# PIC_backpack.net
KiCad netlist of a schematic drawn in EAGLE
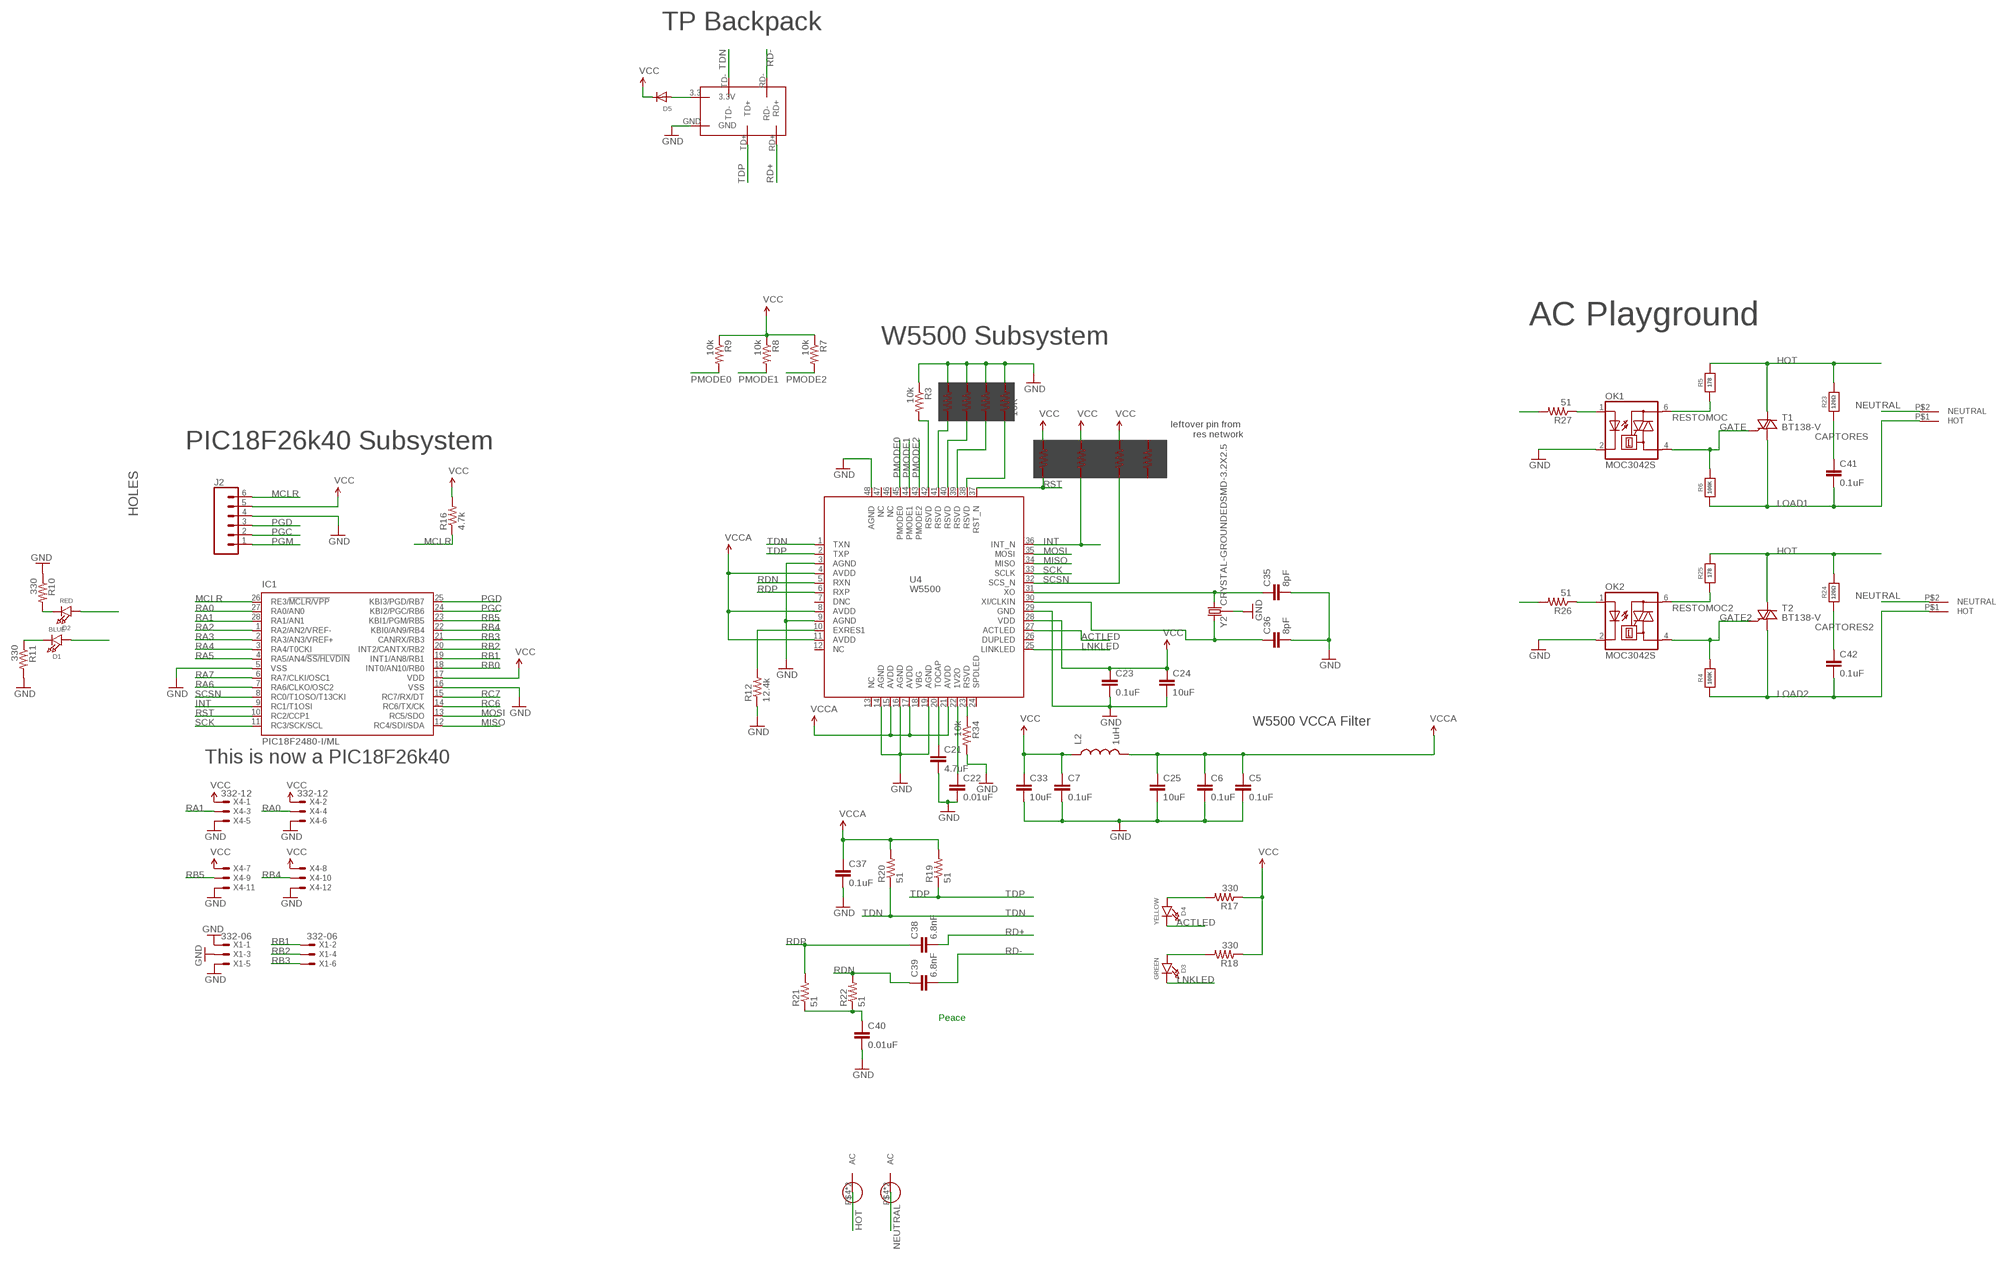
[diagram p0: schematic, sheet 1]

(export (version "E")
  (design (tool "Eeschema 10.0.6"))
  (components
    (comp (ref "C5")
      (value "0.1uF")
      (footprint "eagle-import:0603-CAP")
      (libsource (lib "eagle-import") (part "SparkFun-Passives_CAP0603-CAP"))
    )
    (comp (ref "C6")
      (value "0.1uF")
      (footprint "eagle-import:0603-CAP")
      (libsource (lib "eagle-import") (part "SparkFun-Passives_CAP0603-CAP"))
    )
    (comp (ref "C7")
      (value "0.1uF")
      (footprint "eagle-import:0603-CAP")
      (libsource (lib "eagle-import") (part "SparkFun-Passives_CAP0603-CAP"))
    )
    (comp (ref "C21")
      (value "4.7uF")
      (footprint "eagle-import:0603-CAP")
      (libsource (lib "eagle-import") (part "SparkFun-Passives_CAP0603-CAP"))
    )
    (comp (ref "C22")
      (value "0.01uF")
      (footprint "eagle-import:0603-CAP")
      (libsource (lib "eagle-import") (part "SparkFun-Passives_CAP0603-CAP"))
    )
    (comp (ref "C23")
      (value "0.1uF")
      (footprint "eagle-import:0603-CAP")
      (libsource (lib "eagle-import") (part "SparkFun-Passives_CAP0603-CAP"))
    )
    (comp (ref "C24")
      (value "10uF")
      (footprint "eagle-import:0603-CAP")
      (libsource (lib "eagle-import") (part "SparkFun-Passives_CAP0603-CAP"))
    )
    (comp (ref "C25")
      (value "10uF")
      (footprint "eagle-import:0603-CAP")
      (libsource (lib "eagle-import") (part "SparkFun-Passives_CAP0603-CAP"))
    )
    (comp (ref "C33")
      (value "10uF")
      (footprint "eagle-import:0603-CAP")
      (libsource (lib "eagle-import") (part "SparkFun-Passives_CAP0603-CAP"))
    )
    (comp (ref "C35")
      (value "8pF")
      (footprint "eagle-import:0603-CAP")
      (libsource (lib "eagle-import") (part "SparkFun-Passives_CAP0603-CAP"))
    )
    (comp (ref "C36")
      (value "8pF")
      (footprint "eagle-import:0603-CAP")
      (libsource (lib "eagle-import") (part "SparkFun-Passives_CAP0603-CAP"))
    )
    (comp (ref "C37")
      (value "0.1uF")
      (footprint "eagle-import:0603-CAP")
      (libsource (lib "eagle-import") (part "SparkFun-Passives_CAP0603-CAP"))
    )
    (comp (ref "C38")
      (value "6.8nF")
      (footprint "eagle-import:0603-CAP")
      (libsource (lib "eagle-import") (part "SparkFun-Passives_CAP0603-CAP"))
    )
    (comp (ref "C39")
      (value "6.8nF")
      (footprint "eagle-import:0603-CAP")
      (libsource (lib "eagle-import") (part "SparkFun-Passives_CAP0603-CAP"))
    )
    (comp (ref "C40")
      (value "0.01uF")
      (footprint "eagle-import:0603-CAP")
      (libsource (lib "eagle-import") (part "SparkFun-Passives_CAP0603-CAP"))
    )
    (comp (ref "C41")
      (value "0.1uF")
      (footprint "eagle-import:1210")
      (libsource (lib "eagle-import") (part "CAP1210"))
    )
    (comp (ref "C42")
      (value "0.1uF")
      (footprint "eagle-import:1210")
      (libsource (lib "eagle-import") (part "CAP1210"))
    )
    (comp (ref "D1")
      (value "BLUE")
      (footprint "eagle-import:CHIPLED_0603_NOOUTLINE")
      (libsource (lib "eagle-import") (part "LED0603_NOOUTLINE"))
    )
    (comp (ref "D2")
      (value "RED")
      (footprint "eagle-import:CHIPLED_0603_NOOUTLINE")
      (libsource (lib "eagle-import") (part "LED0603_NOOUTLINE"))
    )
    (comp (ref "D3")
      (value "GREEN")
      (footprint "eagle-import:CHIPLED_0603_NOOUTLINE")
      (libsource (lib "eagle-import") (part "LED0603_NOOUTLINE"))
    )
    (comp (ref "D4")
      (value "YELLOW")
      (footprint "eagle-import:CHIPLED_0603_NOOUTLINE")
      (libsource (lib "eagle-import") (part "LED0603_NOOUTLINE"))
    )
    (comp (ref "D5")
      (value "DIODESOD-123")
      (footprint "eagle-import:SOD-123")
      (libsource (lib "eagle-import") (part "DIODESOD-123"))
    )
    (comp (ref "IC1")
      (value "PIC18F2480-I/ML")
      (footprint "eagle-import:QFN28-ML_6X6MM")
      (fields (field (name "MF") "MICROCHIP"))
      (libsource (lib "eagle-import") (part "PIC18F280-I/ML4"))
    )
    (comp (ref "J2")
      (value "CONN_06NO_SILK_FEMALE_PTH")
      (footprint "eagle-import:1X06_NO_SILK")
      (libsource (lib "eagle-import") (part "CONN_06NO_SILK_FEMALE_PTH"))
    )
    (comp (ref "L2")
      (value "1uH")
      (footprint "eagle-import:0603")
      (libsource (lib "eagle-import") (part "INDUCTOR0603"))
    )
    (comp (ref "OK1")
      (value "MOC3042S")
      (footprint "eagle-import:DIL6-SMD")
      (fields (field (name "MF") "FAIRCHILD SEMICONDUCTOR") (field (name "MPN") "MOC3042SM"))
      (libsource (lib "eagle-import") (part "MOC30S42"))
    )
    (comp (ref "OK2")
      (value "MOC3042S")
      (footprint "eagle-import:DIL6-SMD")
      (fields (field (name "MF") "FAIRCHILD SEMICONDUCTOR") (field (name "MPN") "MOC3042SM"))
      (libsource (lib "eagle-import") (part "MOC30S42"))
    )
    (comp (ref "R1")
      (value "10K")
      (footprint "eagle-import:RESPACK_4X0603")
      (libsource (lib "eagle-import") (part "RESISTOR_4PACK_US"))
    )
    (comp (ref "R2")
      (value "10K")
      (footprint "eagle-import:RESPACK_4X0603")
      (libsource (lib "eagle-import") (part "RESISTOR_4PACK_US"))
    )
    (comp (ref "R3")
      (value "10k")
      (footprint "eagle-import:0603-RES")
      (libsource (lib "eagle-import") (part "RESISTOR0603-RES"))
    )
    (comp (ref "R4")
      (value "100K")
      (footprint "eagle-import:0805_10MGAP")
      (libsource (lib "eagle-import") (part "RESISTOR0805_10MGAP"))
    )
    (comp (ref "R5")
      (value "178")
      (footprint "eagle-import:0805_10MGAP")
      (libsource (lib "eagle-import") (part "RESISTOR0805_10MGAP"))
    )
    (comp (ref "R6")
      (value "100K")
      (footprint "eagle-import:0805_10MGAP")
      (libsource (lib "eagle-import") (part "RESISTOR0805_10MGAP"))
    )
    (comp (ref "R7")
      (value "10k")
      (footprint "eagle-import:0603-RES")
      (libsource (lib "eagle-import") (part "RESISTOR0603-RES"))
    )
    (comp (ref "R8")
      (value "10k")
      (footprint "eagle-import:0603-RES")
      (libsource (lib "eagle-import") (part "RESISTOR0603-RES"))
    )
    (comp (ref "R9")
      (value "10k")
      (footprint "eagle-import:0603-RES")
      (libsource (lib "eagle-import") (part "RESISTOR0603-RES"))
    )
    (comp (ref "R10")
      (value "330")
      (footprint "eagle-import:0603-RES")
      (libsource (lib "eagle-import") (part "RESISTOR0603-RES"))
    )
    (comp (ref "R11")
      (value "330")
      (footprint "eagle-import:0603-RES")
      (libsource (lib "eagle-import") (part "RESISTOR0603-RES"))
    )
    (comp (ref "R12")
      (value "12.4k")
      (footprint "eagle-import:0603-RES")
      (libsource (lib "eagle-import") (part "RESISTOR0603-RES"))
    )
    (comp (ref "R16")
      (value "4.7k")
      (footprint "eagle-import:0603-RES")
      (libsource (lib "eagle-import") (part "RESISTOR0603-RES"))
    )
    (comp (ref "R17")
      (value "330")
      (footprint "eagle-import:0603-RES")
      (libsource (lib "eagle-import") (part "RESISTOR0603-RES"))
    )
    (comp (ref "R18")
      (value "330")
      (footprint "eagle-import:0603-RES")
      (libsource (lib "eagle-import") (part "RESISTOR0603-RES"))
    )
    (comp (ref "R19")
      (value "51")
      (footprint "eagle-import:0603-RES")
      (libsource (lib "eagle-import") (part "RESISTOR0603-RES"))
    )
    (comp (ref "R20")
      (value "51")
      (footprint "eagle-import:0603-RES")
      (libsource (lib "eagle-import") (part "RESISTOR0603-RES"))
    )
    (comp (ref "R21")
      (value "51")
      (footprint "eagle-import:0603-RES")
      (libsource (lib "eagle-import") (part "RESISTOR0603-RES"))
    )
    (comp (ref "R22")
      (value "51")
      (footprint "eagle-import:0603-RES")
      (libsource (lib "eagle-import") (part "RESISTOR0603-RES"))
    )
    (comp (ref "R23")
      (value "120Ω")
      (footprint "eagle-import:0805_10MGAP")
      (libsource (lib "eagle-import") (part "RESISTOR0805_10MGAP"))
    )
    (comp (ref "R24")
      (value "120Ω")
      (footprint "eagle-import:0805_10MGAP")
      (libsource (lib "eagle-import") (part "RESISTOR0805_10MGAP"))
    )
    (comp (ref "R25")
      (value "178")
      (footprint "eagle-import:0805_10MGAP")
      (libsource (lib "eagle-import") (part "RESISTOR0805_10MGAP"))
    )
    (comp (ref "R26")
      (value "51")
      (footprint "eagle-import:0603-RES")
      (libsource (lib "eagle-import") (part "RESISTOR0603-RES"))
    )
    (comp (ref "R27")
      (value "51")
      (footprint "eagle-import:0603-RES")
      (libsource (lib "eagle-import") (part "RESISTOR0603-RES"))
    )
    (comp (ref "R34")
      (value "10k")
      (footprint "eagle-import:0603-RES")
      (libsource (lib "eagle-import") (part "RESISTOR0603-RES"))
    )
    (comp (ref "T1")
      (value "BT138-V")
      (footprint "eagle-import:TO220BV")
      (libsource (lib "eagle-import") (part "BT138-V"))
    )
    (comp (ref "T2")
      (value "BT138-V")
      (footprint "eagle-import:TO220BV")
      (libsource (lib "eagle-import") (part "BT138-V"))
    )
    (comp (ref "U$1")
      (value "TPLINK_BACKPACK")
      (footprint "eagle-import:BACKPACK_WITH_PROTO")
      (libsource (lib "eagle-import") (part "TPLINK_BACKPACK"))
    )
    (comp (ref "U$2")
      (value "AC_BLADE")
      (footprint "eagle-import:AC_BLADE")
      (libsource (lib "eagle-import") (part "AC_BLADE"))
    )
    (comp (ref "U$3")
      (value "AC_BLADE")
      (footprint "eagle-import:AC_BLADE")
      (libsource (lib "eagle-import") (part "AC_BLADE"))
    )
    (comp (ref "U$4")
      (value "AC_TERMINAL")
      (footprint "eagle-import:AC_TERMINAL")
      (libsource (lib "eagle-import") (part "AC_TERMINAL"))
    )
    (comp (ref "U$5")
      (value "AC_TERMINAL")
      (footprint "eagle-import:AC_TERMINAL")
      (libsource (lib "eagle-import") (part "AC_TERMINAL"))
    )
    (comp (ref "U4")
      (value "W5500")
      (footprint "eagle-import:W5500")
      (libsource (lib "eagle-import") (part "W5500"))
    )
    (comp (ref "X1")
      (value "332-06")
      (footprint "eagle-import:332-06")
      (libsource (lib "eagle-import") (part "332-06"))
    )
    (comp (ref "X4")
      (value "332-12")
      (footprint "eagle-import:332-12")
      (libsource (lib "eagle-import") (part "332-12"))
    )
    (comp (ref "Y2")
      (value "CRYSTAL-GROUNDEDSMD-3.2X2.5")
      (footprint "eagle-import:CRYSTAL-SMD-3.2X2.5MM")
      (libsource (lib "eagle-import") (part "CRYSTAL-GROUNDEDSMD-3.2X2.5"))
    )
  )
  (nets
    (net (code "1") (name "/ACTLED") (class "Default")
      (node (ref "D4") (pin "C") (pinfunction "C_C") (pintype "passive"))
      (node (ref "U4") (pin "27") (pinfunction "ACTLED_27") (pintype "passive"))
    )
    (net (code "2") (name "/CAPTORES") (class "Default")
      (node (ref "C41") (pin "1") (pinfunction "1_1") (pintype "passive"))
      (node (ref "R23") (pin "1") (pinfunction "1_1") (pintype "passive"))
    )
    (net (code "3") (name "/CAPTORES2") (class "Default")
      (node (ref "C42") (pin "1") (pinfunction "1_1") (pintype "passive"))
      (node (ref "R24") (pin "1") (pinfunction "1_1") (pintype "passive"))
    )
    (net (code "4") (name "/GATE") (class "Default")
      (node (ref "OK1") (pin "4") (pinfunction "A1_4") (pintype "passive"))
      (node (ref "R6") (pin "2") (pinfunction "2_2") (pintype "passive"))
      (node (ref "T1") (pin "G") (pinfunction "G_G") (pintype "passive"))
    )
    (net (code "5") (name "/GATE2") (class "Default")
      (node (ref "OK2") (pin "4") (pinfunction "A1_4") (pintype "passive"))
      (node (ref "R4") (pin "2") (pinfunction "2_2") (pintype "passive"))
      (node (ref "T2") (pin "G") (pinfunction "G_G") (pintype "passive"))
    )
    (net (code "6") (name "/HOT") (class "Default")
      (node (ref "R23") (pin "2") (pinfunction "2_2") (pintype "passive"))
      (node (ref "R24") (pin "2") (pinfunction "2_2") (pintype "passive"))
      (node (ref "R25") (pin "2") (pinfunction "2_2") (pintype "passive"))
      (node (ref "R5") (pin "2") (pinfunction "2_2") (pintype "passive"))
      (node (ref "T1") (pin "T2") (pinfunction "A2_T2") (pintype "passive"))
      (node (ref "T2") (pin "T2") (pinfunction "A2_T2") (pintype "passive"))
      (node (ref "U$2") (pin "P$4") (pinfunction "AC_P$4") (pintype "bidirectional"))
      (node (ref "U$2") (pin "P$5") (pinfunction "AC_P$5") (pintype "bidirectional"))
    )
    (net (code "7") (name "/INT") (class "Default")
      (node (ref "IC1") (pin "9") (pinfunction "RC1/T1OSI_9") (pintype "bidirectional"))
      (node (ref "R2") (pin "3") (pinfunction "1_3") (pintype "passive"))
      (node (ref "U4") (pin "36") (pinfunction "INT_N_36") (pintype "passive"))
    )
    (net (code "8") (name "/LNKLED") (class "Default")
      (node (ref "D3") (pin "C") (pinfunction "C_C") (pintype "passive"))
      (node (ref "U4") (pin "25") (pinfunction "LINKLED_25") (pintype "passive"))
    )
    (net (code "9") (name "/LOAD1") (class "Default")
      (node (ref "C41") (pin "2") (pinfunction "2_2") (pintype "passive"))
      (node (ref "R6") (pin "1") (pinfunction "1_1") (pintype "passive"))
      (node (ref "T1") (pin "T1") (pinfunction "A1_T1") (pintype "passive"))
      (node (ref "U$5") (pin "P$1") (pinfunction "HOT_P$1") (pintype "bidirectional"))
    )
    (net (code "10") (name "/LOAD2") (class "Default")
      (node (ref "C42") (pin "2") (pinfunction "2_2") (pintype "passive"))
      (node (ref "R4") (pin "1") (pinfunction "1_1") (pintype "passive"))
      (node (ref "T2") (pin "T1") (pinfunction "A1_T1") (pintype "passive"))
      (node (ref "U$4") (pin "P$1") (pinfunction "HOT_P$1") (pintype "bidirectional"))
    )
    (net (code "11") (name "/MCLR") (class "Default")
      (node (ref "IC1") (pin "26") (pinfunction "RE3/~{MCLR/VPP}_26") (pintype "input"))
      (node (ref "J2") (pin "6") (pinfunction "6_6") (pintype "passive"))
      (node (ref "R16") (pin "1") (pinfunction "1_1") (pintype "passive"))
    )
    (net (code "12") (name "/MISO") (class "Default")
      (node (ref "IC1") (pin "12") (pinfunction "RC4/SDI/SDA_12") (pintype "bidirectional"))
      (node (ref "U4") (pin "34") (pinfunction "MISO_34") (pintype "passive"))
    )
    (net (code "13") (name "/MOSI") (class "Default")
      (node (ref "IC1") (pin "13") (pinfunction "RC5/SDO_13") (pintype "bidirectional"))
      (node (ref "U4") (pin "35") (pinfunction "MOSI_35") (pintype "passive"))
    )
    (net (code "14") (name "/NEUTRAL") (class "Default")
      (node (ref "U$3") (pin "P$4") (pinfunction "AC_P$4") (pintype "bidirectional"))
      (node (ref "U$3") (pin "P$5") (pinfunction "AC_P$5") (pintype "bidirectional"))
      (node (ref "U$4") (pin "P$2") (pinfunction "NEUTRAL_P$2") (pintype "bidirectional"))
      (node (ref "U$5") (pin "P$2") (pinfunction "NEUTRAL_P$2") (pintype "bidirectional"))
    )
    (net (code "15") (name "/PGC") (class "Default")
      (node (ref "IC1") (pin "24") (pinfunction "KBI2/PGC/RB6_24") (pintype "bidirectional"))
      (node (ref "J2") (pin "2") (pinfunction "2_2") (pintype "passive"))
    )
    (net (code "16") (name "/PGD") (class "Default")
      (node (ref "IC1") (pin "25") (pinfunction "KBI3/PGD/RB7_25") (pintype "bidirectional"))
      (node (ref "J2") (pin "3") (pinfunction "3_3") (pintype "passive"))
    )
    (net (code "17") (name "/PGM") (class "Default")
      (node (ref "J2") (pin "1") (pinfunction "1_1") (pintype "passive"))
    )
    (net (code "18") (name "/PMODE0") (class "Default")
      (node (ref "R9") (pin "2") (pinfunction "2_2") (pintype "passive"))
      (node (ref "U4") (pin "45") (pinfunction "PMODE0_45") (pintype "passive"))
    )
    (net (code "19") (name "/PMODE1") (class "Default")
      (node (ref "R8") (pin "2") (pinfunction "2_2") (pintype "passive"))
      (node (ref "U4") (pin "44") (pinfunction "PMODE1_44") (pintype "passive"))
    )
    (net (code "20") (name "/PMODE2") (class "Default")
      (node (ref "R7") (pin "2") (pinfunction "2_2") (pintype "passive"))
      (node (ref "U4") (pin "43") (pinfunction "PMODE2_43") (pintype "passive"))
    )
    (net (code "21") (name "/RA0") (class "Default")
      (node (ref "IC1") (pin "27") (pinfunction "RA0/AN0_27") (pintype "bidirectional"))
      (node (ref "X4") (pin "4") (pinfunction "S_4") (pintype "passive"))
    )
    (net (code "22") (name "/RA1") (class "Default")
      (node (ref "IC1") (pin "28") (pinfunction "RA1/AN1_28") (pintype "bidirectional"))
      (node (ref "X4") (pin "3") (pinfunction "S_3") (pintype "passive"))
    )
    (net (code "23") (name "/RA2") (class "Default")
      (node (ref "IC1") (pin "1") (pinfunction "RA2/AN2/VREF-_1") (pintype "bidirectional"))
    )
    (net (code "24") (name "/RA3") (class "Default")
      (node (ref "IC1") (pin "2") (pinfunction "RA3/AN3/VREF+_2") (pintype "bidirectional"))
    )
    (net (code "25") (name "/RA4") (class "Default")
      (node (ref "IC1") (pin "3") (pinfunction "RA4/T0CKI_3") (pintype "bidirectional"))
      (node (ref "R26") (pin "2") (pinfunction "2_2") (pintype "passive"))
    )
    (net (code "26") (name "/RA5") (class "Default")
      (node (ref "IC1") (pin "4") (pinfunction "RA5/AN4/~{SS/HLVDIN}_4") (pintype "bidirectional"))
      (node (ref "R27") (pin "2") (pinfunction "2_2") (pintype "passive"))
    )
    (net (code "27") (name "/RA6") (class "Default")
      (node (ref "IC1") (pin "7") (pinfunction "RA6/CLKO/OSC2_7") (pintype "output"))
    )
    (net (code "28") (name "/RA7") (class "Default")
      (node (ref "IC1") (pin "6") (pinfunction "RA7/CLKI/OSC1_6") (pintype "input"))
    )
    (net (code "29") (name "/RB0") (class "Default")
      (node (ref "IC1") (pin "18") (pinfunction "INT0/AN10/RB0_18") (pintype "bidirectional"))
    )
    (net (code "30") (name "/RB1") (class "Default")
      (node (ref "IC1") (pin "19") (pinfunction "INT1/AN8/RB1_19") (pintype "bidirectional"))
      (node (ref "X1") (pin "2") (pinfunction "S_2") (pintype "passive"))
    )
    (net (code "31") (name "/RB2") (class "Default")
      (node (ref "IC1") (pin "20") (pinfunction "INT2/CANTX/RB2_20") (pintype "bidirectional"))
      (node (ref "X1") (pin "4") (pinfunction "S_4") (pintype "passive"))
    )
    (net (code "32") (name "/RB3") (class "Default")
      (node (ref "IC1") (pin "21") (pinfunction "CANRX/RB3_21") (pintype "bidirectional"))
      (node (ref "X1") (pin "6") (pinfunction "S_6") (pintype "passive"))
    )
    (net (code "33") (name "/RB4") (class "Default")
      (node (ref "IC1") (pin "22") (pinfunction "KBI0/AN9/RB4_22") (pintype "bidirectional"))
      (node (ref "X4") (pin "10") (pinfunction "S_10") (pintype "passive"))
    )
    (net (code "34") (name "/RB5") (class "Default")
      (node (ref "IC1") (pin "23") (pinfunction "KBI1/PGM/RB5_23") (pintype "bidirectional"))
      (node (ref "X4") (pin "9") (pinfunction "S_9") (pintype "passive"))
    )
    (net (code "35") (name "/RC6") (class "Default")
      (node (ref "D2") (pin "A") (pinfunction "A_A") (pintype "passive"))
      (node (ref "IC1") (pin "14") (pinfunction "RC6/TX/CK_14") (pintype "bidirectional"))
    )
    (net (code "36") (name "/RC7") (class "Default")
      (node (ref "D1") (pin "A") (pinfunction "A_A") (pintype "passive"))
      (node (ref "IC1") (pin "15") (pinfunction "RC7/RX/DT_15") (pintype "bidirectional"))
    )
    (net (code "37") (name "/RD+") (class "Default")
      (node (ref "C38") (pin "2") (pinfunction "2_2") (pintype "passive"))
      (node (ref "U$1") (pin "RD+") (pinfunction "RD+_RD+") (pintype "bidirectional"))
    )
    (net (code "38") (name "/RD-") (class "Default")
      (node (ref "C39") (pin "2") (pinfunction "2_2") (pintype "passive"))
      (node (ref "U$1") (pin "RD-") (pinfunction "RD-_RD-") (pintype "bidirectional"))
    )
    (net (code "39") (name "/RDN") (class "Default")
      (node (ref "C39") (pin "1") (pinfunction "1_1") (pintype "passive"))
      (node (ref "R22") (pin "2") (pinfunction "2_2") (pintype "passive"))
      (node (ref "U4") (pin "5") (pinfunction "RXN_5") (pintype "passive"))
    )
    (net (code "40") (name "/RDP") (class "Default")
      (node (ref "C38") (pin "1") (pinfunction "1_1") (pintype "passive"))
      (node (ref "R21") (pin "2") (pinfunction "2_2") (pintype "passive"))
      (node (ref "U4") (pin "6") (pinfunction "RXP_6") (pintype "passive"))
    )
    (net (code "41") (name "/RESTOMOC") (class "Default")
      (node (ref "OK1") (pin "6") (pinfunction "A2_6") (pintype "passive"))
      (node (ref "R5") (pin "1") (pinfunction "1_1") (pintype "passive"))
    )
    (net (code "42") (name "/RESTOMOC2") (class "Default")
      (node (ref "OK2") (pin "6") (pinfunction "A2_6") (pintype "passive"))
      (node (ref "R25") (pin "1") (pinfunction "1_1") (pintype "passive"))
    )
    (net (code "43") (name "/RST") (class "Default")
      (node (ref "IC1") (pin "10") (pinfunction "RC2/CCP1_10") (pintype "bidirectional"))
      (node (ref "R2") (pin "2") (pinfunction "1_2") (pintype "passive"))
      (node (ref "U4") (pin "37") (pinfunction "RST_N_37") (pintype "passive"))
    )
    (net (code "44") (name "/SCK") (class "Default")
      (node (ref "IC1") (pin "11") (pinfunction "RC3/SCK/SCL_11") (pintype "bidirectional"))
      (node (ref "U4") (pin "33") (pinfunction "SCLK_33") (pintype "passive"))
    )
    (net (code "45") (name "/SCSN") (class "Default")
      (node (ref "IC1") (pin "8") (pinfunction "RC0/T1OSO/T13CKI_8") (pintype "bidirectional"))
      (node (ref "R2") (pin "4") (pinfunction "1_4") (pintype "passive"))
      (node (ref "U4") (pin "32") (pinfunction "SCS_N_32") (pintype "passive"))
    )
    (net (code "46") (name "/TDN") (class "Default")
      (node (ref "R20") (pin "1") (pinfunction "1_1") (pintype "passive"))
      (node (ref "U$1") (pin "TD-") (pinfunction "TD-_TD-") (pintype "bidirectional"))
      (node (ref "U4") (pin "1") (pinfunction "TXN_1") (pintype "passive"))
    )
    (net (code "47") (name "/TDP") (class "Default")
      (node (ref "R19") (pin "1") (pinfunction "1_1") (pintype "passive"))
      (node (ref "U$1") (pin "TD+") (pinfunction "TD+_TD+") (pintype "bidirectional"))
      (node (ref "U4") (pin "2") (pinfunction "TXP_2") (pintype "passive"))
    )
    (net (code "48") (name "GND") (class "Default")
      (node (ref "C21") (pin "2") (pinfunction "2_2") (pintype "passive"))
      (node (ref "C22") (pin "2") (pinfunction "2_2") (pintype "passive"))
      (node (ref "C23") (pin "2") (pinfunction "2_2") (pintype "passive"))
      (node (ref "C24") (pin "2") (pinfunction "2_2") (pintype "passive"))
      (node (ref "C25") (pin "2") (pinfunction "2_2") (pintype "passive"))
      (node (ref "C33") (pin "2") (pinfunction "2_2") (pintype "passive"))
      (node (ref "C35") (pin "2") (pinfunction "2_2") (pintype "passive"))
      (node (ref "C36") (pin "2") (pinfunction "2_2") (pintype "passive"))
      (node (ref "C37") (pin "2") (pinfunction "2_2") (pintype "passive"))
      (node (ref "C40") (pin "2") (pinfunction "2_2") (pintype "passive"))
      (node (ref "C5") (pin "2") (pinfunction "2_2") (pintype "passive"))
      (node (ref "C6") (pin "2") (pinfunction "2_2") (pintype "passive"))
      (node (ref "C7") (pin "2") (pinfunction "2_2") (pintype "passive"))
      (node (ref "IC1") (pin "16") (pinfunction "VSS_16") (pintype "power_in"))
      (node (ref "IC1") (pin "5") (pinfunction "VSS_5") (pintype "power_in"))
      (node (ref "J2") (pin "4") (pinfunction "4_4") (pintype "passive"))
      (node (ref "OK1") (pin "2") (pinfunction "C_2") (pintype "passive"))
      (node (ref "OK2") (pin "2") (pinfunction "C_2") (pintype "passive"))
      (node (ref "R1") (pin "5") (pinfunction "2_5") (pintype "passive"))
      (node (ref "R1") (pin "6") (pinfunction "2_6") (pintype "passive"))
      (node (ref "R1") (pin "7") (pinfunction "2_7") (pintype "passive"))
      (node (ref "R1") (pin "8") (pinfunction "2_8") (pintype "passive"))
      (node (ref "R10") (pin "1") (pinfunction "1_1") (pintype "passive"))
      (node (ref "R11") (pin "2") (pinfunction "2_2") (pintype "passive"))
      (node (ref "R12") (pin "1") (pinfunction "1_1") (pintype "passive"))
      (node (ref "R3") (pin "1") (pinfunction "1_1") (pintype "passive"))
      (node (ref "R34") (pin "2") (pinfunction "2_2") (pintype "passive"))
      (node (ref "U$1") (pin "GND") (pinfunction "GND_GND") (pintype "bidirectional"))
      (node (ref "U4") (pin "14") (pinfunction "AGND_14") (pintype "passive"))
      (node (ref "U4") (pin "16") (pinfunction "AGND_16") (pintype "passive"))
      (node (ref "U4") (pin "19") (pinfunction "AGND_19") (pintype "passive"))
      (node (ref "U4") (pin "29") (pinfunction "GND_29") (pintype "passive"))
      (node (ref "U4") (pin "3") (pinfunction "AGND_3") (pintype "passive"))
      (node (ref "U4") (pin "48") (pinfunction "AGND_48") (pintype "passive"))
      (node (ref "U4") (pin "9") (pinfunction "AGND_9") (pintype "passive"))
      (node (ref "X1") (pin "1") (pinfunction "S_1") (pintype "passive"))
      (node (ref "X1") (pin "3") (pinfunction "S_3") (pintype "passive"))
      (node (ref "X1") (pin "5") (pinfunction "S_5") (pintype "passive"))
      (node (ref "X4") (pin "11") (pinfunction "S_11") (pintype "passive"))
      (node (ref "X4") (pin "12") (pinfunction "S_12") (pintype "passive"))
      (node (ref "X4") (pin "5") (pinfunction "S_5") (pintype "passive"))
      (node (ref "X4") (pin "6") (pinfunction "S_6") (pintype "passive"))
      (node (ref "Y2") (pin "2") (pinfunction "3_2") (pintype "passive"))
      (node (ref "Y2") (pin "4") (pinfunction "3_4") (pintype "passive"))
    )
    (net (code "49") (name "Net-(C40-Pad1)") (class "Default")
      (node (ref "C40") (pin "1") (pinfunction "1_1") (pintype "passive"))
      (node (ref "R21") (pin "1") (pinfunction "1_1") (pintype "passive"))
      (node (ref "R22") (pin "1") (pinfunction "1_1") (pintype "passive"))
    )
    (net (code "50") (name "Net-(D1-PadC)") (class "Default")
      (node (ref "D1") (pin "C") (pinfunction "C_C") (pintype "passive"))
      (node (ref "R11") (pin "1") (pinfunction "1_1") (pintype "passive"))
    )
    (net (code "51") (name "Net-(D2-PadC)") (class "Default")
      (node (ref "D2") (pin "C") (pinfunction "C_C") (pintype "passive"))
      (node (ref "R10") (pin "2") (pinfunction "2_2") (pintype "passive"))
    )
    (net (code "52") (name "Net-(D3-PadA)") (class "Default")
      (node (ref "D3") (pin "A") (pinfunction "A_A") (pintype "passive"))
      (node (ref "R18") (pin "2") (pinfunction "2_2") (pintype "passive"))
    )
    (net (code "53") (name "Net-(D4-PadA)") (class "Default")
      (node (ref "D4") (pin "A") (pinfunction "A_A") (pintype "passive"))
      (node (ref "R17") (pin "2") (pinfunction "2_2") (pintype "passive"))
    )
    (net (code "54") (name "Net-(OK1-A)") (class "Default")
      (node (ref "OK1") (pin "1") (pinfunction "A_1") (pintype "passive"))
      (node (ref "R27") (pin "1") (pinfunction "1_1") (pintype "passive"))
    )
    (net (code "55") (name "Net-(OK2-A)") (class "Default")
      (node (ref "OK2") (pin "1") (pinfunction "A_1") (pintype "passive"))
      (node (ref "R26") (pin "1") (pinfunction "1_1") (pintype "passive"))
    )
    (net (code "56") (name "Net-(R1-Pad1)") (class "Default")
      (node (ref "R1") (pin "1") (pinfunction "1_1") (pintype "passive"))
      (node (ref "U4") (pin "41") (pinfunction "RSVD_41") (pintype "passive"))
    )
    (net (code "57") (name "Net-(R1B-1)") (class "Default")
      (node (ref "R1") (pin "2") (pinfunction "1_2") (pintype "passive"))
      (node (ref "U4") (pin "40") (pinfunction "RSVD_40") (pintype "passive"))
    )
    (net (code "58") (name "Net-(R1C-1)") (class "Default")
      (node (ref "R1") (pin "3") (pinfunction "1_3") (pintype "passive"))
      (node (ref "U4") (pin "39") (pinfunction "RSVD_39") (pintype "passive"))
    )
    (net (code "59") (name "Net-(R1D-1)") (class "Default")
      (node (ref "R1") (pin "4") (pinfunction "1_4") (pintype "passive"))
      (node (ref "U4") (pin "38") (pinfunction "RSVD_38") (pintype "passive"))
    )
    (net (code "60") (name "Net-(R3-Pad2)") (class "Default")
      (node (ref "R3") (pin "2") (pinfunction "2_2") (pintype "passive"))
      (node (ref "U4") (pin "42") (pinfunction "RSVD_42") (pintype "passive"))
    )
    (net (code "61") (name "Net-(R34-Pad1)") (class "Default")
      (node (ref "R34") (pin "1") (pinfunction "1_1") (pintype "passive"))
      (node (ref "U4") (pin "23") (pinfunction "RSVD_23") (pintype "passive"))
    )
    (net (code "62") (name "Net-(U$1-3.3V)") (class "Default")
      (node (ref "D5") (pin "A") (pinfunction "A_A") (pintype "passive"))
      (node (ref "U$1") (pin "3.3") (pinfunction "3.3V_3.3") (pintype "bidirectional"))
    )
    (net (code "63") (name "Net-(U4-1V2O)") (class "Default")
      (node (ref "C22") (pin "1") (pinfunction "1_1") (pintype "passive"))
      (node (ref "U4") (pin "22") (pinfunction "1V2O_22") (pintype "passive"))
    )
    (net (code "64") (name "Net-(U4-EXRES1)") (class "Default")
      (node (ref "R12") (pin "2") (pinfunction "2_2") (pintype "passive"))
      (node (ref "U4") (pin "10") (pinfunction "EXRES1_10") (pintype "passive"))
    )
    (net (code "65") (name "Net-(U4-TOCAP)") (class "Default")
      (node (ref "C21") (pin "1") (pinfunction "1_1") (pintype "passive"))
      (node (ref "U4") (pin "20") (pinfunction "TOCAP_20") (pintype "passive"))
    )
    (net (code "66") (name "Net-(U4-XI{slash}CLKIN)") (class "Default")
      (node (ref "C36") (pin "1") (pinfunction "1_1") (pintype "passive"))
      (node (ref "U4") (pin "30") (pinfunction "XI/CLKIN_30") (pintype "passive"))
      (node (ref "Y2") (pin "1") (pinfunction "1_1") (pintype "passive"))
    )
    (net (code "67") (name "Net-(U4-XO)") (class "Default")
      (node (ref "C35") (pin "1") (pinfunction "1_1") (pintype "passive"))
      (node (ref "U4") (pin "31") (pinfunction "XO_31") (pintype "passive"))
      (node (ref "Y2") (pin "3") (pinfunction "2_3") (pintype "passive"))
    )
    (net (code "68") (name "VCC") (class "Default")
      (node (ref "C23") (pin "1") (pinfunction "1_1") (pintype "passive"))
      (node (ref "C24") (pin "1") (pinfunction "1_1") (pintype "passive"))
      (node (ref "C33") (pin "1") (pinfunction "1_1") (pintype "passive"))
      (node (ref "C7") (pin "1") (pinfunction "1_1") (pintype "passive"))
      (node (ref "D5") (pin "C") (pinfunction "C_C") (pintype "passive"))
      (node (ref "IC1") (pin "17") (pinfunction "VDD_17") (pintype "power_in"))
      (node (ref "J2") (pin "5") (pinfunction "5_5") (pintype "passive"))
      (node (ref "L2") (pin "1") (pinfunction "1_1") (pintype "passive"))
      (node (ref "R16") (pin "2") (pinfunction "2_2") (pintype "passive"))
      (node (ref "R17") (pin "1") (pinfunction "1_1") (pintype "passive"))
      (node (ref "R18") (pin "1") (pinfunction "1_1") (pintype "passive"))
      (node (ref "R2") (pin "5") (pinfunction "2_5") (pintype "passive"))
      (node (ref "R2") (pin "6") (pinfunction "2_6") (pintype "passive"))
      (node (ref "R2") (pin "7") (pinfunction "2_7") (pintype "passive"))
      (node (ref "R7") (pin "1") (pinfunction "1_1") (pintype "passive"))
      (node (ref "R8") (pin "1") (pinfunction "1_1") (pintype "passive"))
      (node (ref "R9") (pin "1") (pinfunction "1_1") (pintype "passive"))
      (node (ref "U4") (pin "28") (pinfunction "VDD_28") (pintype "passive"))
      (node (ref "X4") (pin "1") (pinfunction "S_1") (pintype "passive"))
      (node (ref "X4") (pin "2") (pinfunction "S_2") (pintype "passive"))
      (node (ref "X4") (pin "7") (pinfunction "S_7") (pintype "passive"))
      (node (ref "X4") (pin "8") (pinfunction "S_8") (pintype "passive"))
    )
    (net (code "69") (name "VCCA") (class "Default")
      (node (ref "C25") (pin "1") (pinfunction "1_1") (pintype "passive"))
      (node (ref "C37") (pin "1") (pinfunction "1_1") (pintype "passive"))
      (node (ref "C5") (pin "1") (pinfunction "1_1") (pintype "passive"))
      (node (ref "C6") (pin "1") (pinfunction "1_1") (pintype "passive"))
      (node (ref "L2") (pin "2") (pinfunction "2_2") (pintype "passive"))
      (node (ref "R19") (pin "2") (pinfunction "2_2") (pintype "passive"))
      (node (ref "R20") (pin "2") (pinfunction "2_2") (pintype "passive"))
      (node (ref "U4") (pin "11") (pinfunction "AVDD_11") (pintype "passive"))
      (node (ref "U4") (pin "15") (pinfunction "AVDD_15") (pintype "passive"))
      (node (ref "U4") (pin "17") (pinfunction "AVDD_17") (pintype "passive"))
      (node (ref "U4") (pin "21") (pinfunction "AVDD_21") (pintype "passive"))
      (node (ref "U4") (pin "4") (pinfunction "AVDD_4") (pintype "passive"))
      (node (ref "U4") (pin "8") (pinfunction "AVDD_8") (pintype "passive"))
    )
    (net (code "70") (name "unconnected-(R2-Pad1)") (class "Default")
      (node (ref "R2") (pin "1") (pinfunction "1_1") (pintype "passive"))
    )
    (net (code "71") (name "unconnected-(R2A-2-Pad8)") (class "Default")
      (node (ref "R2") (pin "8") (pinfunction "2_8") (pintype "passive"))
    )
    (net (code "72") (name "unconnected-(U4-DNC-Pad7)") (class "Default")
      (node (ref "U4") (pin "7") (pinfunction "DNC_7") (pintype "passive"))
    )
    (net (code "73") (name "unconnected-(U4-DUPLED-Pad26)") (class "Default")
      (node (ref "U4") (pin "26") (pinfunction "DUPLED_26") (pintype "passive"))
    )
    (net (code "74") (name "unconnected-(U4-NC-Pad12)") (class "Default")
      (node (ref "U4") (pin "12") (pinfunction "NC_12") (pintype "passive"))
    )
    (net (code "75") (name "unconnected-(U4-NC-Pad13)") (class "Default")
      (node (ref "U4") (pin "13") (pinfunction "NC_13") (pintype "passive"))
    )
    (net (code "76") (name "unconnected-(U4-NC-Pad46)") (class "Default")
      (node (ref "U4") (pin "46") (pinfunction "NC_46") (pintype "passive"))
    )
    (net (code "77") (name "unconnected-(U4-NC-Pad47)") (class "Default")
      (node (ref "U4") (pin "47") (pinfunction "NC_47") (pintype "passive"))
    )
    (net (code "78") (name "unconnected-(U4-SPDLED-Pad24)") (class "Default")
      (node (ref "U4") (pin "24") (pinfunction "SPDLED_24") (pintype "passive"))
    )
    (net (code "79") (name "unconnected-(U4-VBG-Pad18)") (class "Default")
      (node (ref "U4") (pin "18") (pinfunction "VBG_18") (pintype "passive"))
    )
  )
)
